# ConBoard_Top.net
KiCad netlist of a schematic drawn in Altium Designer
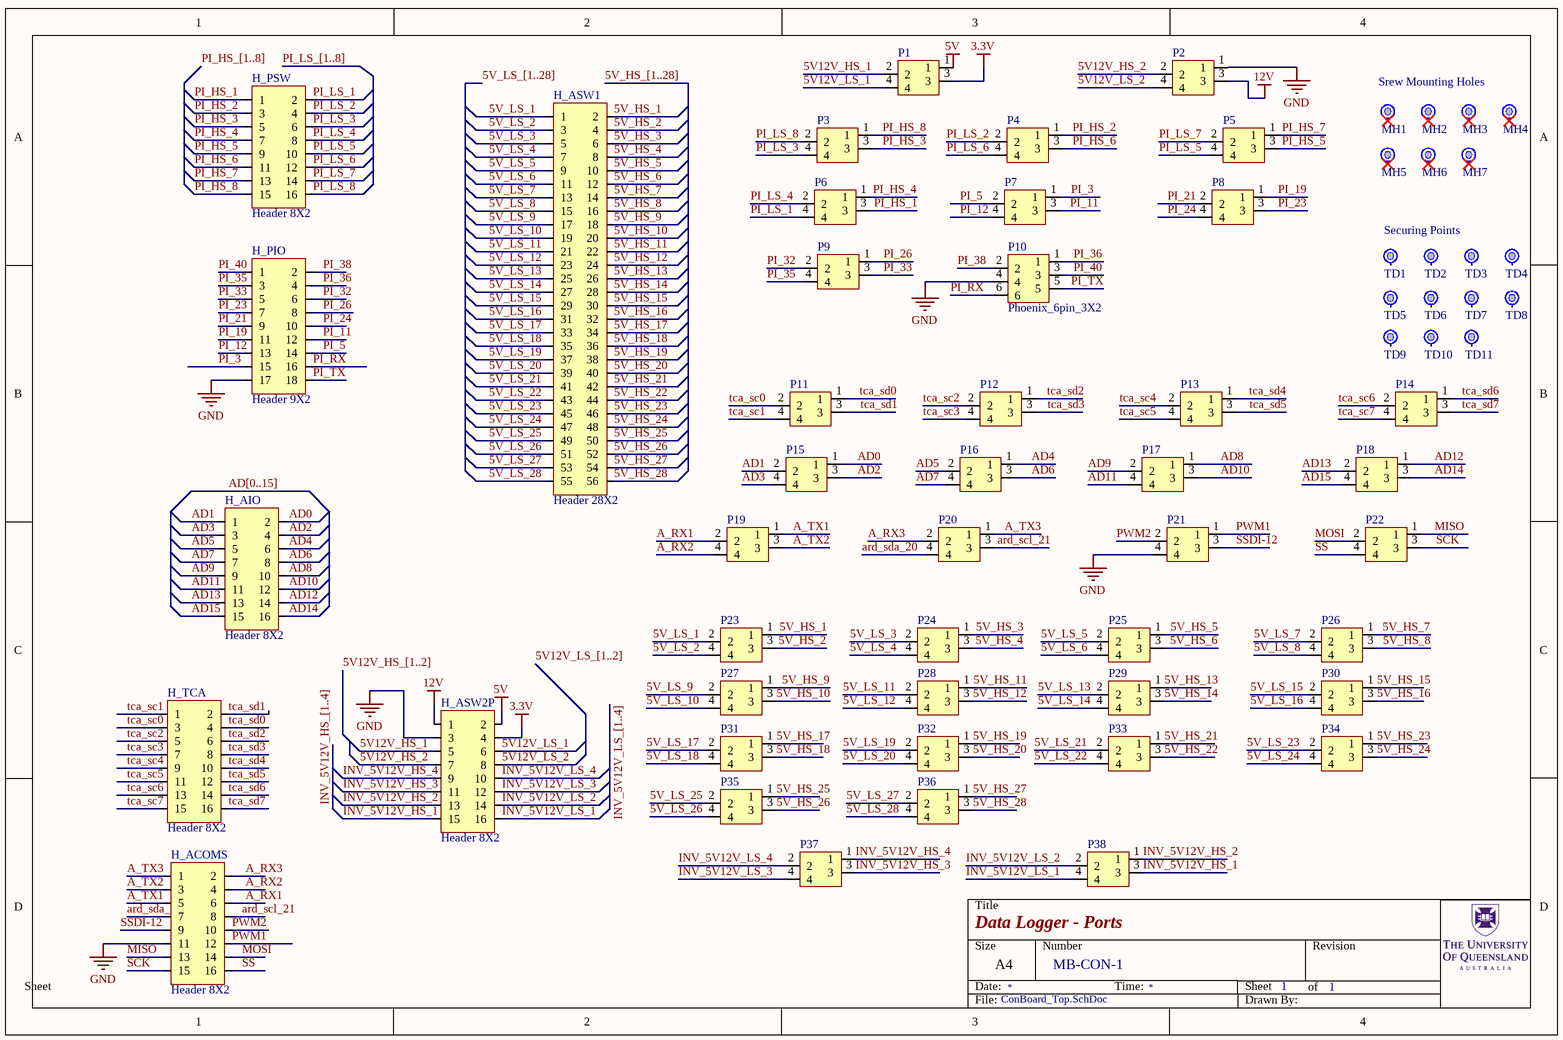
[diagram p0: ConBoard_Top.SchDoc]

(export (version "E")
  (design (tool "Eeschema 10.0.6"))
  (components
    (comp (ref "H_ACOMS")
      (value "Header 8X2")
      (footprint "HDR2X8")
      (description "Header, 8-Pin, Dual row")
      (fields (field (name "PUBLISHER") "Altium Limited"))
      (libsource (lib "Miscellaneous Connectors") (part "Header 8X2"))
    )
    (comp (ref "H_AIO")
      (value "Header 8X2")
      (footprint "HDR2X8")
      (description "Header, 8-Pin, Dual row")
      (fields (field (name "PUBLISHER") "Altium Limited"))
      (libsource (lib "Miscellaneous Connectors") (part "Header 8X2"))
    )
    (comp (ref "H_ASW1")
      (value "Header 28X2")
      (footprint "HDR2X28")
      (description "Header, 28-Pin, Dual row")
      (fields (field (name "PUBLISHER") "Altium Limited"))
      (libsource (lib "Data_logger_v3") (part "Header 28X2"))
    )
    (comp (ref "H_ASW2P")
      (value "Header 8X2")
      (footprint "HDR2X8")
      (description "Header, 8-Pin, Dual row")
      (fields (field (name "PUBLISHER") "Altium Limited"))
      (libsource (lib "Miscellaneous Connectors") (part "Header 8X2"))
    )
    (comp (ref "H_PIO")
      (value "Header 9X2")
      (footprint "HDR2X9")
      (description "Header, 9-Pin, Dual row")
      (fields (field (name "PUBLISHER") "Altium Limited"))
      (libsource (lib "Miscellaneous Connectors") (part "Header 9X2"))
    )
    (comp (ref "H_PSW")
      (value "Header 8X2")
      (footprint "HDR2X8")
      (description "Header, 8-Pin, Dual row")
      (fields (field (name "PUBLISHER") "Altium Limited"))
      (libsource (lib "Miscellaneous Connectors") (part "Header 8X2"))
    )
    (comp (ref "H_TCA")
      (value "Header 8X2")
      (footprint "HDR2X8")
      (description "Header, 8-Pin, Dual row")
      (fields (field (name "PUBLISHER") "Altium Limited"))
      (libsource (lib "Miscellaneous Connectors") (part "Header 8X2"))
    )
    (comp (ref "MH1")
      (value "MOUNTING_HOLE")
      (footprint "M3")
      (libsource (lib "Data_logger_v3") (part "MOUNTING_HOLE"))
    )
    (comp (ref "MH2")
      (value "MOUNTING_HOLE")
      (footprint "M3")
      (libsource (lib "Data_logger_v3") (part "MOUNTING_HOLE"))
    )
    (comp (ref "MH3")
      (value "MOUNTING_HOLE")
      (footprint "M3")
      (libsource (lib "Data_logger_v3") (part "MOUNTING_HOLE"))
    )
    (comp (ref "MH4")
      (value "MOUNTING_HOLE")
      (footprint "M3")
      (libsource (lib "Data_logger_v3") (part "MOUNTING_HOLE"))
    )
    (comp (ref "MH5")
      (value "MOUNTING_HOLE")
      (footprint "M3")
      (libsource (lib "Data_logger_v3") (part "MOUNTING_HOLE"))
    )
    (comp (ref "MH6")
      (value "MOUNTING_HOLE")
      (footprint "M3")
      (libsource (lib "Data_logger_v3") (part "MOUNTING_HOLE"))
    )
    (comp (ref "MH7")
      (value "MOUNTING_HOLE")
      (footprint "M3")
      (libsource (lib "Data_logger_v3") (part "MOUNTING_HOLE"))
    )
    (comp (ref "P1")
      (value "Phoenix_4pin_2X2")
      (footprint "MKKDSN_4PIN-2POS_5.08PITCH_1.5WIRE")
      (libsource (lib "Datalogger") (part "Phoenix_4pin_2X2"))
    )
    (comp (ref "P2")
      (value "Phoenix_4pin_2X2")
      (footprint "MKKDSN_4PIN-2POS_5.08PITCH_1.5WIRE")
      (libsource (lib "Datalogger") (part "Phoenix_4pin_2X2"))
    )
    (comp (ref "P3")
      (value "Phoenix_4pin_2X2")
      (footprint "MKKDSN_4PIN-2POS_5.08PITCH_1.5WIRE")
      (libsource (lib "Datalogger") (part "Phoenix_4pin_2X2"))
    )
    (comp (ref "P4")
      (value "Phoenix_4pin_2X2")
      (footprint "MKKDSN_4PIN-2POS_5.08PITCH_1.5WIRE")
      (libsource (lib "Datalogger") (part "Phoenix_4pin_2X2"))
    )
    (comp (ref "P5")
      (value "Phoenix_4pin_2X2")
      (footprint "MKKDSN_4PIN-2POS_5.08PITCH_1.5WIRE")
      (libsource (lib "Datalogger") (part "Phoenix_4pin_2X2"))
    )
    (comp (ref "P6")
      (value "Phoenix_4pin_2X2")
      (footprint "MKKDSN_4PIN-2POS_5.08PITCH_1.5WIRE")
      (libsource (lib "Datalogger") (part "Phoenix_4pin_2X2"))
    )
    (comp (ref "P7")
      (value "Phoenix_4pin_2X2")
      (footprint "MKKDSN_4PIN-2POS_5.08PITCH_1.5WIRE")
      (libsource (lib "Datalogger") (part "Phoenix_4pin_2X2"))
    )
    (comp (ref "P8")
      (value "Phoenix_4pin_2X2")
      (footprint "MKKDSN_4PIN-2POS_5.08PITCH_1.5WIRE")
      (libsource (lib "Datalogger") (part "Phoenix_4pin_2X2"))
    )
    (comp (ref "P9")
      (value "Phoenix_4pin_2X2")
      (footprint "MKKDSN_4PIN-2POS_5.08PITCH_1.5WIRE")
      (libsource (lib "Datalogger") (part "Phoenix_4pin_2X2"))
    )
    (comp (ref "P10")
      (value "Phoenix_6pin_3X2")
      (footprint "MKKDSN_6PIN-3POS_5.08PITCH_1.5WIRE")
      (libsource (lib "Datalogger") (part "Phoenix_6pin_3X2"))
    )
    (comp (ref "P11")
      (value "Phoenix_4pin_2X2")
      (footprint "MKKDSN_4PIN-2POS_5.08PITCH_1.5WIRE")
      (libsource (lib "Datalogger") (part "Phoenix_4pin_2X2"))
    )
    (comp (ref "P12")
      (value "Phoenix_4pin_2X2")
      (footprint "MKKDSN_4PIN-2POS_5.08PITCH_1.5WIRE")
      (libsource (lib "Datalogger") (part "Phoenix_4pin_2X2"))
    )
    (comp (ref "P13")
      (value "Phoenix_4pin_2X2")
      (footprint "MKKDSN_4PIN-2POS_5.08PITCH_1.5WIRE")
      (libsource (lib "Datalogger") (part "Phoenix_4pin_2X2"))
    )
    (comp (ref "P14")
      (value "Phoenix_4pin_2X2")
      (footprint "MKKDSN_4PIN-2POS_5.08PITCH_1.5WIRE")
      (libsource (lib "Datalogger") (part "Phoenix_4pin_2X2"))
    )
    (comp (ref "P15")
      (value "Phoenix_4pin_2X2")
      (footprint "MKKDSN_4PIN-2POS_5.08PITCH_1.5WIRE")
      (libsource (lib "Datalogger") (part "Phoenix_4pin_2X2"))
    )
    (comp (ref "P16")
      (value "Phoenix_4pin_2X2")
      (footprint "MKKDSN_4PIN-2POS_5.08PITCH_1.5WIRE")
      (libsource (lib "Datalogger") (part "Phoenix_4pin_2X2"))
    )
    (comp (ref "P17")
      (value "Phoenix_4pin_2X2")
      (footprint "MKKDSN_4PIN-2POS_5.08PITCH_1.5WIRE")
      (libsource (lib "Datalogger") (part "Phoenix_4pin_2X2"))
    )
    (comp (ref "P18")
      (value "Phoenix_4pin_2X2")
      (footprint "MKKDSN_4PIN-2POS_5.08PITCH_1.5WIRE")
      (libsource (lib "Datalogger") (part "Phoenix_4pin_2X2"))
    )
    (comp (ref "P19")
      (value "Phoenix_4pin_2X2")
      (footprint "MKKDSN_4PIN-2POS_5.08PITCH_1.5WIRE")
      (libsource (lib "Datalogger") (part "Phoenix_4pin_2X2"))
    )
    (comp (ref "P20")
      (value "Phoenix_4pin_2X2")
      (footprint "MKKDSN_4PIN-2POS_5.08PITCH_1.5WIRE")
      (libsource (lib "Datalogger") (part "Phoenix_4pin_2X2"))
    )
    (comp (ref "P21")
      (value "Phoenix_4pin_2X2")
      (footprint "MKKDSN_4PIN-2POS_5.08PITCH_1.5WIRE")
      (libsource (lib "Datalogger") (part "Phoenix_4pin_2X2"))
    )
    (comp (ref "P22")
      (value "Phoenix_4pin_2X2")
      (footprint "MKKDSN_4PIN-2POS_5.08PITCH_1.5WIRE")
      (libsource (lib "Datalogger") (part "Phoenix_4pin_2X2"))
    )
    (comp (ref "P23")
      (value "Phoenix_4pin_2X2")
      (footprint "MKKDSN_4PIN-2POS_5.08PITCH_1.5WIRE")
      (libsource (lib "Datalogger") (part "Phoenix_4pin_2X2"))
    )
    (comp (ref "P24")
      (value "Phoenix_4pin_2X2")
      (footprint "MKKDSN_4PIN-2POS_5.08PITCH_1.5WIRE")
      (libsource (lib "Datalogger") (part "Phoenix_4pin_2X2"))
    )
    (comp (ref "P25")
      (value "Phoenix_4pin_2X2")
      (footprint "MKKDSN_4PIN-2POS_5.08PITCH_1.5WIRE")
      (libsource (lib "Datalogger") (part "Phoenix_4pin_2X2"))
    )
    (comp (ref "P26")
      (value "Phoenix_4pin_2X2")
      (footprint "MKKDSN_4PIN-2POS_5.08PITCH_1.5WIRE")
      (libsource (lib "Datalogger") (part "Phoenix_4pin_2X2"))
    )
    (comp (ref "P27")
      (value "Phoenix_4pin_2X2")
      (footprint "MKKDSN_4PIN-2POS_5.08PITCH_1.5WIRE")
      (libsource (lib "Datalogger") (part "Phoenix_4pin_2X2"))
    )
    (comp (ref "P28")
      (value "Phoenix_4pin_2X2")
      (footprint "MKKDSN_4PIN-2POS_5.08PITCH_1.5WIRE")
      (libsource (lib "Datalogger") (part "Phoenix_4pin_2X2"))
    )
    (comp (ref "P29")
      (value "Phoenix_4pin_2X2")
      (footprint "MKKDSN_4PIN-2POS_5.08PITCH_1.5WIRE")
      (libsource (lib "Datalogger") (part "Phoenix_4pin_2X2"))
    )
    (comp (ref "P30")
      (value "Phoenix_4pin_2X2")
      (footprint "MKKDSN_4PIN-2POS_5.08PITCH_1.5WIRE")
      (libsource (lib "Datalogger") (part "Phoenix_4pin_2X2"))
    )
    (comp (ref "P31")
      (value "Phoenix_4pin_2X2")
      (footprint "MKKDSN_4PIN-2POS_5.08PITCH_1.5WIRE")
      (libsource (lib "Datalogger") (part "Phoenix_4pin_2X2"))
    )
    (comp (ref "P32")
      (value "Phoenix_4pin_2X2")
      (footprint "MKKDSN_4PIN-2POS_5.08PITCH_1.5WIRE")
      (libsource (lib "Datalogger") (part "Phoenix_4pin_2X2"))
    )
    (comp (ref "P33")
      (value "Phoenix_4pin_2X2")
      (footprint "MKKDSN_4PIN-2POS_5.08PITCH_1.5WIRE")
      (libsource (lib "Datalogger") (part "Phoenix_4pin_2X2"))
    )
    (comp (ref "P34")
      (value "Phoenix_4pin_2X2")
      (footprint "MKKDSN_4PIN-2POS_5.08PITCH_1.5WIRE")
      (libsource (lib "Datalogger") (part "Phoenix_4pin_2X2"))
    )
    (comp (ref "P35")
      (value "Phoenix_4pin_2X2")
      (footprint "MKKDSN_4PIN-2POS_5.08PITCH_1.5WIRE")
      (libsource (lib "Datalogger") (part "Phoenix_4pin_2X2"))
    )
    (comp (ref "P36")
      (value "Phoenix_4pin_2X2")
      (footprint "MKKDSN_4PIN-2POS_5.08PITCH_1.5WIRE")
      (libsource (lib "Datalogger") (part "Phoenix_4pin_2X2"))
    )
    (comp (ref "P37")
      (value "Phoenix_4pin_2X2")
      (footprint "MKKDSN_4PIN-2POS_5.08PITCH_1.5WIRE")
      (libsource (lib "Datalogger") (part "Phoenix_4pin_2X2"))
    )
    (comp (ref "P38")
      (value "Phoenix_4pin_2X2")
      (footprint "MKKDSN_4PIN-2POS_5.08PITCH_1.5WIRE")
      (libsource (lib "Datalogger") (part "Phoenix_4pin_2X2"))
    )
    (comp (ref "TD1")
      (value "TIEDOWNS")
      (footprint "M3")
      (libsource (lib "Data_logger_v3") (part "MOUNTING_HOLE"))
    )
    (comp (ref "TD2")
      (value "TIEDOWNS")
      (footprint "M3")
      (libsource (lib "Data_logger_v3") (part "MOUNTING_HOLE"))
    )
    (comp (ref "TD3")
      (value "TIEDOWNS")
      (footprint "M3")
      (libsource (lib "Data_logger_v3") (part "MOUNTING_HOLE"))
    )
    (comp (ref "TD4")
      (value "TIEDOWNS")
      (footprint "M3")
      (libsource (lib "Data_logger_v3") (part "MOUNTING_HOLE"))
    )
    (comp (ref "TD5")
      (value "TIEDOWNS")
      (footprint "M3")
      (libsource (lib "Data_logger_v3") (part "MOUNTING_HOLE"))
    )
    (comp (ref "TD6")
      (value "TIEDOWNS")
      (footprint "M3")
      (libsource (lib "Data_logger_v3") (part "MOUNTING_HOLE"))
    )
    (comp (ref "TD7")
      (value "TIEDOWNS")
      (footprint "M3")
      (libsource (lib "Data_logger_v3") (part "MOUNTING_HOLE"))
    )
    (comp (ref "TD8")
      (value "TIEDOWNS")
      (footprint "M3")
      (libsource (lib "Data_logger_v3") (part "MOUNTING_HOLE"))
    )
    (comp (ref "TD9")
      (value "TIEDOWNS")
      (footprint "M3")
      (libsource (lib "Data_logger_v3") (part "MOUNTING_HOLE"))
    )
    (comp (ref "TD10")
      (value "TIEDOWNS")
      (footprint "M3")
      (libsource (lib "Data_logger_v3") (part "MOUNTING_HOLE"))
    )
    (comp (ref "TD11")
      (value "TIEDOWNS")
      (footprint "M3")
      (libsource (lib "Data_logger_v3") (part "MOUNTING_HOLE"))
    )
  )
  (nets
    (net (code "1") (name "/5V12V_HS_1") (class "Default")
      (node (ref "H_ASW2P") (pin "5") (pinfunction "5_5") (pintype "passive"))
      (node (ref "P1") (pin "2") (pinfunction "2_2") (pintype "passive"))
    )
    (net (code "2") (name "/5V12V_HS_2") (class "Default")
      (node (ref "H_ASW2P") (pin "7") (pinfunction "7_7") (pintype "passive"))
      (node (ref "P2") (pin "2") (pinfunction "2_2") (pintype "passive"))
    )
    (net (code "4") (name "/5V12V_LS_1") (class "Default")
      (node (ref "H_ASW2P") (pin "6") (pinfunction "6_6") (pintype "passive"))
      (node (ref "P1") (pin "4") (pinfunction "4_4") (pintype "passive"))
    )
    (net (code "5") (name "/5V12V_LS_2") (class "Default")
      (node (ref "H_ASW2P") (pin "8") (pinfunction "8_8") (pintype "passive"))
      (node (ref "P2") (pin "4") (pinfunction "4_4") (pintype "passive"))
    )
    (net (code "7") (name "/5V_HS_1") (class "Default")
      (node (ref "H_ASW1") (pin "2") (pinfunction "2_2") (pintype "passive"))
      (node (ref "P23") (pin "1") (pinfunction "1_1") (pintype "passive"))
    )
    (net (code "8") (name "/5V_HS_2") (class "Default")
      (node (ref "H_ASW1") (pin "4") (pinfunction "4_4") (pintype "passive"))
      (node (ref "P23") (pin "3") (pinfunction "3_3") (pintype "passive"))
    )
    (net (code "9") (name "/5V_HS_3") (class "Default")
      (node (ref "H_ASW1") (pin "6") (pinfunction "6_6") (pintype "passive"))
      (node (ref "P24") (pin "1") (pinfunction "1_1") (pintype "passive"))
    )
    (net (code "10") (name "/5V_HS_4") (class "Default")
      (node (ref "H_ASW1") (pin "8") (pinfunction "8_8") (pintype "passive"))
      (node (ref "P24") (pin "3") (pinfunction "3_3") (pintype "passive"))
    )
    (net (code "11") (name "/5V_HS_5") (class "Default")
      (node (ref "H_ASW1") (pin "10") (pinfunction "10_10") (pintype "passive"))
      (node (ref "P25") (pin "1") (pinfunction "1_1") (pintype "passive"))
    )
    (net (code "12") (name "/5V_HS_6") (class "Default")
      (node (ref "H_ASW1") (pin "12") (pinfunction "12_12") (pintype "passive"))
      (node (ref "P25") (pin "3") (pinfunction "3_3") (pintype "passive"))
    )
    (net (code "13") (name "/5V_HS_7") (class "Default")
      (node (ref "H_ASW1") (pin "14") (pinfunction "14_14") (pintype "passive"))
      (node (ref "P26") (pin "1") (pinfunction "1_1") (pintype "passive"))
    )
    (net (code "14") (name "/5V_HS_8") (class "Default")
      (node (ref "H_ASW1") (pin "16") (pinfunction "16_16") (pintype "passive"))
      (node (ref "P26") (pin "3") (pinfunction "3_3") (pintype "passive"))
    )
    (net (code "15") (name "/5V_HS_9") (class "Default")
      (node (ref "H_ASW1") (pin "18") (pinfunction "18_18") (pintype "passive"))
      (node (ref "P27") (pin "1") (pinfunction "1_1") (pintype "passive"))
    )
    (net (code "16") (name "/5V_HS_10") (class "Default")
      (node (ref "H_ASW1") (pin "20") (pinfunction "20_20") (pintype "passive"))
      (node (ref "P27") (pin "3") (pinfunction "3_3") (pintype "passive"))
    )
    (net (code "17") (name "/5V_HS_11") (class "Default")
      (node (ref "H_ASW1") (pin "22") (pinfunction "22_22") (pintype "passive"))
      (node (ref "P28") (pin "1") (pinfunction "1_1") (pintype "passive"))
    )
    (net (code "18") (name "/5V_HS_12") (class "Default")
      (node (ref "H_ASW1") (pin "24") (pinfunction "24_24") (pintype "passive"))
      (node (ref "P28") (pin "3") (pinfunction "3_3") (pintype "passive"))
    )
    (net (code "19") (name "/5V_HS_13") (class "Default")
      (node (ref "H_ASW1") (pin "26") (pinfunction "26_26") (pintype "passive"))
      (node (ref "P29") (pin "1") (pinfunction "1_1") (pintype "passive"))
    )
    (net (code "20") (name "/5V_HS_14") (class "Default")
      (node (ref "H_ASW1") (pin "28") (pinfunction "28_28") (pintype "passive"))
      (node (ref "P29") (pin "3") (pinfunction "3_3") (pintype "passive"))
    )
    (net (code "21") (name "/5V_HS_15") (class "Default")
      (node (ref "H_ASW1") (pin "30") (pinfunction "30_30") (pintype "passive"))
      (node (ref "P30") (pin "1") (pinfunction "1_1") (pintype "passive"))
    )
    (net (code "22") (name "/5V_HS_16") (class "Default")
      (node (ref "H_ASW1") (pin "32") (pinfunction "32_32") (pintype "passive"))
      (node (ref "P30") (pin "3") (pinfunction "3_3") (pintype "passive"))
    )
    (net (code "23") (name "/5V_HS_17") (class "Default")
      (node (ref "H_ASW1") (pin "34") (pinfunction "34_34") (pintype "passive"))
      (node (ref "P31") (pin "1") (pinfunction "1_1") (pintype "passive"))
    )
    (net (code "24") (name "/5V_HS_18") (class "Default")
      (node (ref "H_ASW1") (pin "36") (pinfunction "36_36") (pintype "passive"))
      (node (ref "P31") (pin "3") (pinfunction "3_3") (pintype "passive"))
    )
    (net (code "25") (name "/5V_HS_19") (class "Default")
      (node (ref "H_ASW1") (pin "38") (pinfunction "38_38") (pintype "passive"))
      (node (ref "P32") (pin "1") (pinfunction "1_1") (pintype "passive"))
    )
    (net (code "26") (name "/5V_HS_20") (class "Default")
      (node (ref "H_ASW1") (pin "40") (pinfunction "40_40") (pintype "passive"))
      (node (ref "P32") (pin "3") (pinfunction "3_3") (pintype "passive"))
    )
    (net (code "27") (name "/5V_HS_21") (class "Default")
      (node (ref "H_ASW1") (pin "42") (pinfunction "42_42") (pintype "passive"))
      (node (ref "P33") (pin "1") (pinfunction "1_1") (pintype "passive"))
    )
    (net (code "28") (name "/5V_HS_22") (class "Default")
      (node (ref "H_ASW1") (pin "44") (pinfunction "44_44") (pintype "passive"))
      (node (ref "P33") (pin "3") (pinfunction "3_3") (pintype "passive"))
    )
    (net (code "29") (name "/5V_HS_23") (class "Default")
      (node (ref "H_ASW1") (pin "46") (pinfunction "46_46") (pintype "passive"))
      (node (ref "P34") (pin "1") (pinfunction "1_1") (pintype "passive"))
    )
    (net (code "30") (name "/5V_HS_24") (class "Default")
      (node (ref "H_ASW1") (pin "48") (pinfunction "48_48") (pintype "passive"))
      (node (ref "P34") (pin "3") (pinfunction "3_3") (pintype "passive"))
    )
    (net (code "31") (name "/5V_HS_25") (class "Default")
      (node (ref "H_ASW1") (pin "50") (pinfunction "50_50") (pintype "passive"))
      (node (ref "P35") (pin "1") (pinfunction "1_1") (pintype "passive"))
    )
    (net (code "32") (name "/5V_HS_26") (class "Default")
      (node (ref "H_ASW1") (pin "52") (pinfunction "52_52") (pintype "passive"))
      (node (ref "P35") (pin "3") (pinfunction "3_3") (pintype "passive"))
    )
    (net (code "33") (name "/5V_HS_27") (class "Default")
      (node (ref "H_ASW1") (pin "54") (pinfunction "54_54") (pintype "passive"))
      (node (ref "P36") (pin "1") (pinfunction "1_1") (pintype "passive"))
    )
    (net (code "34") (name "/5V_HS_28") (class "Default")
      (node (ref "H_ASW1") (pin "56") (pinfunction "56_56") (pintype "passive"))
      (node (ref "P36") (pin "3") (pinfunction "3_3") (pintype "passive"))
    )
    (net (code "36") (name "/5V_LS_1") (class "Default")
      (node (ref "H_ASW1") (pin "1") (pinfunction "1_1") (pintype "passive"))
      (node (ref "P23") (pin "2") (pinfunction "2_2") (pintype "passive"))
    )
    (net (code "37") (name "/5V_LS_2") (class "Default")
      (node (ref "H_ASW1") (pin "3") (pinfunction "3_3") (pintype "passive"))
      (node (ref "P23") (pin "4") (pinfunction "4_4") (pintype "passive"))
    )
    (net (code "38") (name "/5V_LS_3") (class "Default")
      (node (ref "H_ASW1") (pin "5") (pinfunction "5_5") (pintype "passive"))
      (node (ref "P24") (pin "2") (pinfunction "2_2") (pintype "passive"))
    )
    (net (code "39") (name "/5V_LS_4") (class "Default")
      (node (ref "H_ASW1") (pin "7") (pinfunction "7_7") (pintype "passive"))
      (node (ref "P24") (pin "4") (pinfunction "4_4") (pintype "passive"))
    )
    (net (code "40") (name "/5V_LS_5") (class "Default")
      (node (ref "H_ASW1") (pin "9") (pinfunction "9_9") (pintype "passive"))
      (node (ref "P25") (pin "2") (pinfunction "2_2") (pintype "passive"))
    )
    (net (code "41") (name "/5V_LS_6") (class "Default")
      (node (ref "H_ASW1") (pin "11") (pinfunction "11_11") (pintype "passive"))
      (node (ref "P25") (pin "4") (pinfunction "4_4") (pintype "passive"))
    )
    (net (code "42") (name "/5V_LS_7") (class "Default")
      (node (ref "H_ASW1") (pin "13") (pinfunction "13_13") (pintype "passive"))
      (node (ref "P26") (pin "2") (pinfunction "2_2") (pintype "passive"))
    )
    (net (code "43") (name "/5V_LS_8") (class "Default")
      (node (ref "H_ASW1") (pin "15") (pinfunction "15_15") (pintype "passive"))
      (node (ref "P26") (pin "4") (pinfunction "4_4") (pintype "passive"))
    )
    (net (code "44") (name "/5V_LS_9") (class "Default")
      (node (ref "H_ASW1") (pin "17") (pinfunction "17_17") (pintype "passive"))
      (node (ref "P27") (pin "2") (pinfunction "2_2") (pintype "passive"))
    )
    (net (code "45") (name "/5V_LS_10") (class "Default")
      (node (ref "H_ASW1") (pin "19") (pinfunction "19_19") (pintype "passive"))
      (node (ref "P27") (pin "4") (pinfunction "4_4") (pintype "passive"))
    )
    (net (code "46") (name "/5V_LS_11") (class "Default")
      (node (ref "H_ASW1") (pin "21") (pinfunction "21_21") (pintype "passive"))
      (node (ref "P28") (pin "2") (pinfunction "2_2") (pintype "passive"))
    )
    (net (code "47") (name "/5V_LS_12") (class "Default")
      (node (ref "H_ASW1") (pin "23") (pinfunction "23_23") (pintype "passive"))
      (node (ref "P28") (pin "4") (pinfunction "4_4") (pintype "passive"))
    )
    (net (code "48") (name "/5V_LS_13") (class "Default")
      (node (ref "H_ASW1") (pin "25") (pinfunction "25_25") (pintype "passive"))
      (node (ref "P29") (pin "2") (pinfunction "2_2") (pintype "passive"))
    )
    (net (code "49") (name "/5V_LS_14") (class "Default")
      (node (ref "H_ASW1") (pin "27") (pinfunction "27_27") (pintype "passive"))
      (node (ref "P29") (pin "4") (pinfunction "4_4") (pintype "passive"))
    )
    (net (code "50") (name "/5V_LS_15") (class "Default")
      (node (ref "H_ASW1") (pin "29") (pinfunction "29_29") (pintype "passive"))
      (node (ref "P30") (pin "2") (pinfunction "2_2") (pintype "passive"))
    )
    (net (code "51") (name "/5V_LS_16") (class "Default")
      (node (ref "H_ASW1") (pin "31") (pinfunction "31_31") (pintype "passive"))
      (node (ref "P30") (pin "4") (pinfunction "4_4") (pintype "passive"))
    )
    (net (code "52") (name "/5V_LS_17") (class "Default")
      (node (ref "H_ASW1") (pin "33") (pinfunction "33_33") (pintype "passive"))
      (node (ref "P31") (pin "2") (pinfunction "2_2") (pintype "passive"))
    )
    (net (code "53") (name "/5V_LS_18") (class "Default")
      (node (ref "H_ASW1") (pin "35") (pinfunction "35_35") (pintype "passive"))
      (node (ref "P31") (pin "4") (pinfunction "4_4") (pintype "passive"))
    )
    (net (code "54") (name "/5V_LS_19") (class "Default")
      (node (ref "H_ASW1") (pin "37") (pinfunction "37_37") (pintype "passive"))
      (node (ref "P32") (pin "2") (pinfunction "2_2") (pintype "passive"))
    )
    (net (code "55") (name "/5V_LS_20") (class "Default")
      (node (ref "H_ASW1") (pin "39") (pinfunction "39_39") (pintype "passive"))
      (node (ref "P32") (pin "4") (pinfunction "4_4") (pintype "passive"))
    )
    (net (code "56") (name "/5V_LS_21") (class "Default")
      (node (ref "H_ASW1") (pin "41") (pinfunction "41_41") (pintype "passive"))
      (node (ref "P33") (pin "2") (pinfunction "2_2") (pintype "passive"))
    )
    (net (code "57") (name "/5V_LS_22") (class "Default")
      (node (ref "H_ASW1") (pin "43") (pinfunction "43_43") (pintype "passive"))
      (node (ref "P33") (pin "4") (pinfunction "4_4") (pintype "passive"))
    )
    (net (code "58") (name "/5V_LS_23") (class "Default")
      (node (ref "H_ASW1") (pin "45") (pinfunction "45_45") (pintype "passive"))
      (node (ref "P34") (pin "2") (pinfunction "2_2") (pintype "passive"))
    )
    (net (code "59") (name "/5V_LS_24") (class "Default")
      (node (ref "H_ASW1") (pin "47") (pinfunction "47_47") (pintype "passive"))
      (node (ref "P34") (pin "4") (pinfunction "4_4") (pintype "passive"))
    )
    (net (code "60") (name "/5V_LS_25") (class "Default")
      (node (ref "H_ASW1") (pin "49") (pinfunction "49_49") (pintype "passive"))
      (node (ref "P35") (pin "2") (pinfunction "2_2") (pintype "passive"))
    )
    (net (code "61") (name "/5V_LS_26") (class "Default")
      (node (ref "H_ASW1") (pin "51") (pinfunction "51_51") (pintype "passive"))
      (node (ref "P35") (pin "4") (pinfunction "4_4") (pintype "passive"))
    )
    (net (code "62") (name "/5V_LS_27") (class "Default")
      (node (ref "H_ASW1") (pin "53") (pinfunction "53_53") (pintype "passive"))
      (node (ref "P36") (pin "2") (pinfunction "2_2") (pintype "passive"))
    )
    (net (code "63") (name "/5V_LS_28") (class "Default")
      (node (ref "H_ASW1") (pin "55") (pinfunction "55_55") (pintype "passive"))
      (node (ref "P36") (pin "4") (pinfunction "4_4") (pintype "passive"))
    )
    (net (code "65") (name "/AD0") (class "Default")
      (node (ref "H_AIO") (pin "2") (pinfunction "2_2") (pintype "passive"))
      (node (ref "P15") (pin "1") (pinfunction "1_1") (pintype "passive"))
    )
    (net (code "66") (name "/AD1") (class "Default")
      (node (ref "H_AIO") (pin "1") (pinfunction "1_1") (pintype "passive"))
      (node (ref "P15") (pin "2") (pinfunction "2_2") (pintype "passive"))
    )
    (net (code "67") (name "/AD2") (class "Default")
      (node (ref "H_AIO") (pin "4") (pinfunction "4_4") (pintype "passive"))
      (node (ref "P15") (pin "3") (pinfunction "3_3") (pintype "passive"))
    )
    (net (code "68") (name "/AD3") (class "Default")
      (node (ref "H_AIO") (pin "3") (pinfunction "3_3") (pintype "passive"))
      (node (ref "P15") (pin "4") (pinfunction "4_4") (pintype "passive"))
    )
    (net (code "69") (name "/AD4") (class "Default")
      (node (ref "H_AIO") (pin "6") (pinfunction "6_6") (pintype "passive"))
      (node (ref "P16") (pin "1") (pinfunction "1_1") (pintype "passive"))
    )
    (net (code "70") (name "/AD5") (class "Default")
      (node (ref "H_AIO") (pin "5") (pinfunction "5_5") (pintype "passive"))
      (node (ref "P16") (pin "2") (pinfunction "2_2") (pintype "passive"))
    )
    (net (code "71") (name "/AD6") (class "Default")
      (node (ref "H_AIO") (pin "8") (pinfunction "8_8") (pintype "passive"))
      (node (ref "P16") (pin "3") (pinfunction "3_3") (pintype "passive"))
    )
    (net (code "72") (name "/AD7") (class "Default")
      (node (ref "H_AIO") (pin "7") (pinfunction "7_7") (pintype "passive"))
      (node (ref "P16") (pin "4") (pinfunction "4_4") (pintype "passive"))
    )
    (net (code "73") (name "/AD8") (class "Default")
      (node (ref "H_AIO") (pin "10") (pinfunction "10_10") (pintype "passive"))
      (node (ref "P17") (pin "1") (pinfunction "1_1") (pintype "passive"))
    )
    (net (code "74") (name "/AD9") (class "Default")
      (node (ref "H_AIO") (pin "9") (pinfunction "9_9") (pintype "passive"))
      (node (ref "P17") (pin "2") (pinfunction "2_2") (pintype "passive"))
    )
    (net (code "75") (name "/AD10") (class "Default")
      (node (ref "H_AIO") (pin "12") (pinfunction "12_12") (pintype "passive"))
      (node (ref "P17") (pin "3") (pinfunction "3_3") (pintype "passive"))
    )
    (net (code "76") (name "/AD11") (class "Default")
      (node (ref "H_AIO") (pin "11") (pinfunction "11_11") (pintype "passive"))
      (node (ref "P17") (pin "4") (pinfunction "4_4") (pintype "passive"))
    )
    (net (code "77") (name "/AD12") (class "Default")
      (node (ref "H_AIO") (pin "14") (pinfunction "14_14") (pintype "passive"))
      (node (ref "P18") (pin "1") (pinfunction "1_1") (pintype "passive"))
    )
    (net (code "78") (name "/AD13") (class "Default")
      (node (ref "H_AIO") (pin "13") (pinfunction "13_13") (pintype "passive"))
      (node (ref "P18") (pin "2") (pinfunction "2_2") (pintype "passive"))
    )
    (net (code "79") (name "/AD14") (class "Default")
      (node (ref "H_AIO") (pin "16") (pinfunction "16_16") (pintype "passive"))
      (node (ref "P18") (pin "3") (pinfunction "3_3") (pintype "passive"))
    )
    (net (code "80") (name "/AD15") (class "Default")
      (node (ref "H_AIO") (pin "15") (pinfunction "15_15") (pintype "passive"))
      (node (ref "P18") (pin "4") (pinfunction "4_4") (pintype "passive"))
    )
    (net (code "82") (name "/A_RX1") (class "Default")
      (node (ref "H_ACOMS") (pin "6") (pinfunction "6_6") (pintype "passive"))
      (node (ref "P19") (pin "2") (pinfunction "2_2") (pintype "passive"))
    )
    (net (code "83") (name "/A_RX2") (class "Default")
      (node (ref "H_ACOMS") (pin "4") (pinfunction "4_4") (pintype "passive"))
      (node (ref "P19") (pin "4") (pinfunction "4_4") (pintype "passive"))
    )
    (net (code "84") (name "/A_RX3") (class "Default")
      (node (ref "H_ACOMS") (pin "2") (pinfunction "2_2") (pintype "passive"))
      (node (ref "P20") (pin "2") (pinfunction "2_2") (pintype "passive"))
    )
    (net (code "85") (name "/A_TX1") (class "Default")
      (node (ref "H_ACOMS") (pin "5") (pinfunction "5_5") (pintype "passive"))
      (node (ref "P19") (pin "1") (pinfunction "1_1") (pintype "passive"))
    )
    (net (code "86") (name "/A_TX2") (class "Default")
      (node (ref "H_ACOMS") (pin "3") (pinfunction "3_3") (pintype "passive"))
      (node (ref "P19") (pin "3") (pinfunction "3_3") (pintype "passive"))
    )
    (net (code "87") (name "/A_TX3") (class "Default")
      (node (ref "H_ACOMS") (pin "1") (pinfunction "1_1") (pintype "passive"))
      (node (ref "P20") (pin "1") (pinfunction "1_1") (pintype "passive"))
    )
    (net (code "88") (name "/INV_5V12V_HS_1") (class "Default")
      (node (ref "H_ASW2P") (pin "15") (pinfunction "15_15") (pintype "passive"))
      (node (ref "P38") (pin "3") (pinfunction "3_3") (pintype "passive"))
    )
    (net (code "89") (name "/INV_5V12V_HS_2") (class "Default")
      (node (ref "H_ASW2P") (pin "13") (pinfunction "13_13") (pintype "passive"))
      (node (ref "P38") (pin "1") (pinfunction "1_1") (pintype "passive"))
    )
    (net (code "90") (name "/INV_5V12V_HS_3") (class "Default")
      (node (ref "H_ASW2P") (pin "11") (pinfunction "11_11") (pintype "passive"))
      (node (ref "P37") (pin "3") (pinfunction "3_3") (pintype "passive"))
    )
    (net (code "91") (name "/INV_5V12V_HS_4") (class "Default")
      (node (ref "H_ASW2P") (pin "9") (pinfunction "9_9") (pintype "passive"))
      (node (ref "P37") (pin "1") (pinfunction "1_1") (pintype "passive"))
    )
    (net (code "93") (name "/INV_5V12V_LS_1") (class "Default")
      (node (ref "H_ASW2P") (pin "16") (pinfunction "16_16") (pintype "passive"))
      (node (ref "P38") (pin "4") (pinfunction "4_4") (pintype "passive"))
    )
    (net (code "94") (name "/INV_5V12V_LS_2") (class "Default")
      (node (ref "H_ASW2P") (pin "14") (pinfunction "14_14") (pintype "passive"))
      (node (ref "P38") (pin "2") (pinfunction "2_2") (pintype "passive"))
    )
    (net (code "95") (name "/INV_5V12V_LS_3") (class "Default")
      (node (ref "H_ASW2P") (pin "12") (pinfunction "12_12") (pintype "passive"))
      (node (ref "P37") (pin "4") (pinfunction "4_4") (pintype "passive"))
    )
    (net (code "96") (name "/INV_5V12V_LS_4") (class "Default")
      (node (ref "H_ASW2P") (pin "10") (pinfunction "10_10") (pintype "passive"))
      (node (ref "P37") (pin "2") (pinfunction "2_2") (pintype "passive"))
    )
    (net (code "98") (name "/MISO") (class "Default")
      (node (ref "H_ACOMS") (pin "13") (pinfunction "13_13") (pintype "passive"))
      (node (ref "P22") (pin "1") (pinfunction "1_1") (pintype "passive"))
    )
    (net (code "99") (name "/MOSI") (class "Default")
      (node (ref "H_ACOMS") (pin "14") (pinfunction "14_14") (pintype "passive"))
      (node (ref "P22") (pin "2") (pinfunction "2_2") (pintype "passive"))
    )
    (net (code "100") (name "/PI_3") (class "Default")
      (node (ref "H_PIO") (pin "15") (pinfunction "15_15") (pintype "passive"))
      (node (ref "P7") (pin "1") (pinfunction "1_1") (pintype "passive"))
    )
    (net (code "101") (name "/PI_5") (class "Default")
      (node (ref "H_PIO") (pin "14") (pinfunction "14_14") (pintype "passive"))
      (node (ref "P7") (pin "2") (pinfunction "2_2") (pintype "passive"))
    )
    (net (code "102") (name "/PI_11") (class "Default")
      (node (ref "H_PIO") (pin "12") (pinfunction "12_12") (pintype "passive"))
      (node (ref "P7") (pin "3") (pinfunction "3_3") (pintype "passive"))
    )
    (net (code "103") (name "/PI_12") (class "Default")
      (node (ref "H_PIO") (pin "13") (pinfunction "13_13") (pintype "passive"))
      (node (ref "P7") (pin "4") (pinfunction "4_4") (pintype "passive"))
    )
    (net (code "104") (name "/PI_19") (class "Default")
      (node (ref "H_PIO") (pin "11") (pinfunction "11_11") (pintype "passive"))
      (node (ref "P8") (pin "1") (pinfunction "1_1") (pintype "passive"))
    )
    (net (code "105") (name "/PI_21") (class "Default")
      (node (ref "H_PIO") (pin "9") (pinfunction "9_9") (pintype "passive"))
      (node (ref "P8") (pin "2") (pinfunction "2_2") (pintype "passive"))
    )
    (net (code "106") (name "/PI_23") (class "Default")
      (node (ref "H_PIO") (pin "7") (pinfunction "7_7") (pintype "passive"))
      (node (ref "P8") (pin "3") (pinfunction "3_3") (pintype "passive"))
    )
    (net (code "107") (name "/PI_24") (class "Default")
      (node (ref "H_PIO") (pin "10") (pinfunction "10_10") (pintype "passive"))
      (node (ref "P8") (pin "4") (pinfunction "4_4") (pintype "passive"))
    )
    (net (code "108") (name "/PI_26") (class "Default")
      (node (ref "H_PIO") (pin "8") (pinfunction "8_8") (pintype "passive"))
      (node (ref "P9") (pin "1") (pinfunction "1_1") (pintype "passive"))
    )
    (net (code "109") (name "/PI_32") (class "Default")
      (node (ref "H_PIO") (pin "6") (pinfunction "6_6") (pintype "passive"))
      (node (ref "P9") (pin "2") (pinfunction "2_2") (pintype "passive"))
    )
    (net (code "110") (name "/PI_33") (class "Default")
      (node (ref "H_PIO") (pin "5") (pinfunction "5_5") (pintype "passive"))
      (node (ref "P9") (pin "3") (pinfunction "3_3") (pintype "passive"))
    )
    (net (code "111") (name "/PI_35") (class "Default")
      (node (ref "H_PIO") (pin "3") (pinfunction "3_3") (pintype "passive"))
      (node (ref "P9") (pin "4") (pinfunction "4_4") (pintype "passive"))
    )
    (net (code "112") (name "/PI_36") (class "Default")
      (node (ref "H_PIO") (pin "4") (pinfunction "4_4") (pintype "passive"))
      (node (ref "P10") (pin "1") (pinfunction "1_1") (pintype "passive"))
    )
    (net (code "113") (name "/PI_38") (class "Default")
      (node (ref "H_PIO") (pin "2") (pinfunction "2_2") (pintype "passive"))
      (node (ref "P10") (pin "2") (pinfunction "2_2") (pintype "passive"))
    )
    (net (code "114") (name "/PI_40") (class "Default")
      (node (ref "H_PIO") (pin "1") (pinfunction "1_1") (pintype "passive"))
      (node (ref "P10") (pin "3") (pinfunction "3_3") (pintype "passive"))
    )
    (net (code "115") (name "/PI_HS_1") (class "Default")
      (node (ref "H_PSW") (pin "1") (pinfunction "1_1") (pintype "passive"))
      (node (ref "P6") (pin "3") (pinfunction "3_3") (pintype "passive"))
    )
    (net (code "116") (name "/PI_HS_2") (class "Default")
      (node (ref "H_PSW") (pin "3") (pinfunction "3_3") (pintype "passive"))
      (node (ref "P4") (pin "1") (pinfunction "1_1") (pintype "passive"))
    )
    (net (code "117") (name "/PI_HS_3") (class "Default")
      (node (ref "H_PSW") (pin "5") (pinfunction "5_5") (pintype "passive"))
      (node (ref "P3") (pin "3") (pinfunction "3_3") (pintype "passive"))
    )
    (net (code "118") (name "/PI_HS_4") (class "Default")
      (node (ref "H_PSW") (pin "7") (pinfunction "7_7") (pintype "passive"))
      (node (ref "P6") (pin "1") (pinfunction "1_1") (pintype "passive"))
    )
    (net (code "119") (name "/PI_HS_5") (class "Default")
      (node (ref "H_PSW") (pin "9") (pinfunction "9_9") (pintype "passive"))
      (node (ref "P5") (pin "3") (pinfunction "3_3") (pintype "passive"))
    )
    (net (code "120") (name "/PI_HS_6") (class "Default")
      (node (ref "H_PSW") (pin "11") (pinfunction "11_11") (pintype "passive"))
      (node (ref "P4") (pin "3") (pinfunction "3_3") (pintype "passive"))
    )
    (net (code "121") (name "/PI_HS_7") (class "Default")
      (node (ref "H_PSW") (pin "13") (pinfunction "13_13") (pintype "passive"))
      (node (ref "P5") (pin "1") (pinfunction "1_1") (pintype "passive"))
    )
    (net (code "122") (name "/PI_HS_8") (class "Default")
      (node (ref "H_PSW") (pin "15") (pinfunction "15_15") (pintype "passive"))
      (node (ref "P3") (pin "1") (pinfunction "1_1") (pintype "passive"))
    )
    (net (code "124") (name "/PI_LS_1") (class "Default")
      (node (ref "H_PSW") (pin "2") (pinfunction "2_2") (pintype "passive"))
      (node (ref "P6") (pin "4") (pinfunction "4_4") (pintype "passive"))
    )
    (net (code "125") (name "/PI_LS_2") (class "Default")
      (node (ref "H_PSW") (pin "4") (pinfunction "4_4") (pintype "passive"))
      (node (ref "P4") (pin "2") (pinfunction "2_2") (pintype "passive"))
    )
    (net (code "126") (name "/PI_LS_3") (class "Default")
      (node (ref "H_PSW") (pin "6") (pinfunction "6_6") (pintype "passive"))
      (node (ref "P3") (pin "4") (pinfunction "4_4") (pintype "passive"))
    )
    (net (code "127") (name "/PI_LS_4") (class "Default")
      (node (ref "H_PSW") (pin "8") (pinfunction "8_8") (pintype "passive"))
      (node (ref "P6") (pin "2") (pinfunction "2_2") (pintype "passive"))
    )
    (net (code "128") (name "/PI_LS_5") (class "Default")
      (node (ref "H_PSW") (pin "10") (pinfunction "10_10") (pintype "passive"))
      (node (ref "P5") (pin "4") (pinfunction "4_4") (pintype "passive"))
    )
    (net (code "129") (name "/PI_LS_6") (class "Default")
      (node (ref "H_PSW") (pin "12") (pinfunction "12_12") (pintype "passive"))
      (node (ref "P4") (pin "4") (pinfunction "4_4") (pintype "passive"))
    )
    (net (code "130") (name "/PI_LS_7") (class "Default")
      (node (ref "H_PSW") (pin "14") (pinfunction "14_14") (pintype "passive"))
      (node (ref "P5") (pin "2") (pinfunction "2_2") (pintype "passive"))
    )
    (net (code "131") (name "/PI_LS_8") (class "Default")
      (node (ref "H_PSW") (pin "16") (pinfunction "16_16") (pintype "passive"))
      (node (ref "P3") (pin "2") (pinfunction "2_2") (pintype "passive"))
    )
    (net (code "133") (name "/PI_RX") (class "Default")
      (node (ref "H_PIO") (pin "16") (pinfunction "16_16") (pintype "passive"))
      (node (ref "P10") (pin "6") (pinfunction "6_6") (pintype "passive"))
    )
    (net (code "134") (name "/PI_TX") (class "Default")
      (node (ref "H_PIO") (pin "18") (pinfunction "18_18") (pintype "passive"))
      (node (ref "P10") (pin "5") (pinfunction "5_5") (pintype "passive"))
    )
    (net (code "135") (name "/PWM1") (class "Default")
      (node (ref "H_ACOMS") (pin "12") (pinfunction "12_12") (pintype "passive"))
      (node (ref "P21") (pin "1") (pinfunction "1_1") (pintype "passive"))
    )
    (net (code "136") (name "/PWM2") (class "Default")
      (node (ref "H_ACOMS") (pin "10") (pinfunction "10_10") (pintype "passive"))
      (node (ref "P21") (pin "2") (pinfunction "2_2") (pintype "passive"))
    )
    (net (code "137") (name "/SCK") (class "Default")
      (node (ref "H_ACOMS") (pin "15") (pinfunction "15_15") (pintype "passive"))
      (node (ref "P22") (pin "3") (pinfunction "3_3") (pintype "passive"))
    )
    (net (code "138") (name "/SS") (class "Default")
      (node (ref "H_ACOMS") (pin "16") (pinfunction "16_16") (pintype "passive"))
      (node (ref "P22") (pin "4") (pinfunction "4_4") (pintype "passive"))
    )
    (net (code "139") (name "/SSDI-12") (class "Default")
      (node (ref "H_ACOMS") (pin "9") (pinfunction "9_9") (pintype "passive"))
      (node (ref "P21") (pin "3") (pinfunction "3_3") (pintype "passive"))
    )
    (net (code "140") (name "/ard_scl_21") (class "Default")
      (node (ref "H_ACOMS") (pin "8") (pinfunction "8_8") (pintype "passive"))
      (node (ref "P20") (pin "3") (pinfunction "3_3") (pintype "passive"))
    )
    (net (code "141") (name "/ard_sda_20") (class "Default")
      (node (ref "H_ACOMS") (pin "7") (pinfunction "7_7") (pintype "passive"))
      (node (ref "P20") (pin "4") (pinfunction "4_4") (pintype "passive"))
    )
    (net (code "142") (name "/tca_sc0") (class "Default")
      (node (ref "H_TCA") (pin "3") (pinfunction "3_3") (pintype "passive"))
      (node (ref "P11") (pin "2") (pinfunction "2_2") (pintype "passive"))
    )
    (net (code "143") (name "/tca_sc1") (class "Default")
      (node (ref "H_TCA") (pin "1") (pinfunction "1_1") (pintype "passive"))
      (node (ref "P11") (pin "4") (pinfunction "4_4") (pintype "passive"))
    )
    (net (code "144") (name "/tca_sc2") (class "Default")
      (node (ref "H_TCA") (pin "5") (pinfunction "5_5") (pintype "passive"))
      (node (ref "P12") (pin "2") (pinfunction "2_2") (pintype "passive"))
    )
    (net (code "145") (name "/tca_sc3") (class "Default")
      (node (ref "H_TCA") (pin "7") (pinfunction "7_7") (pintype "passive"))
      (node (ref "P12") (pin "4") (pinfunction "4_4") (pintype "passive"))
    )
    (net (code "146") (name "/tca_sc4") (class "Default")
      (node (ref "H_TCA") (pin "9") (pinfunction "9_9") (pintype "passive"))
      (node (ref "P13") (pin "2") (pinfunction "2_2") (pintype "passive"))
    )
    (net (code "147") (name "/tca_sc5") (class "Default")
      (node (ref "H_TCA") (pin "11") (pinfunction "11_11") (pintype "passive"))
      (node (ref "P13") (pin "4") (pinfunction "4_4") (pintype "passive"))
    )
    (net (code "148") (name "/tca_sc6") (class "Default")
      (node (ref "H_TCA") (pin "13") (pinfunction "13_13") (pintype "passive"))
      (node (ref "P14") (pin "2") (pinfunction "2_2") (pintype "passive"))
    )
    (net (code "149") (name "/tca_sc7") (class "Default")
      (node (ref "H_TCA") (pin "15") (pinfunction "15_15") (pintype "passive"))
      (node (ref "P14") (pin "4") (pinfunction "4_4") (pintype "passive"))
    )
    (net (code "150") (name "/tca_sd0") (class "Default")
      (node (ref "H_TCA") (pin "4") (pinfunction "4_4") (pintype "passive"))
      (node (ref "P11") (pin "1") (pinfunction "1_1") (pintype "passive"))
    )
    (net (code "151") (name "/tca_sd1") (class "Default")
      (node (ref "H_TCA") (pin "2") (pinfunction "2_2") (pintype "passive"))
      (node (ref "P11") (pin "3") (pinfunction "3_3") (pintype "passive"))
    )
    (net (code "152") (name "/tca_sd2") (class "Default")
      (node (ref "H_TCA") (pin "6") (pinfunction "6_6") (pintype "passive"))
      (node (ref "P12") (pin "1") (pinfunction "1_1") (pintype "passive"))
    )
    (net (code "153") (name "/tca_sd3") (class "Default")
      (node (ref "H_TCA") (pin "8") (pinfunction "8_8") (pintype "passive"))
      (node (ref "P12") (pin "3") (pinfunction "3_3") (pintype "passive"))
    )
    (net (code "154") (name "/tca_sd4") (class "Default")
      (node (ref "H_TCA") (pin "10") (pinfunction "10_10") (pintype "passive"))
      (node (ref "P13") (pin "1") (pinfunction "1_1") (pintype "passive"))
    )
    (net (code "155") (name "/tca_sd5") (class "Default")
      (node (ref "H_TCA") (pin "12") (pinfunction "12_12") (pintype "passive"))
      (node (ref "P13") (pin "3") (pinfunction "3_3") (pintype "passive"))
    )
    (net (code "156") (name "/tca_sd6") (class "Default")
      (node (ref "H_TCA") (pin "14") (pinfunction "14_14") (pintype "passive"))
      (node (ref "P14") (pin "1") (pinfunction "1_1") (pintype "passive"))
    )
    (net (code "157") (name "/tca_sd7") (class "Default")
      (node (ref "H_TCA") (pin "16") (pinfunction "16_16") (pintype "passive"))
      (node (ref "P14") (pin "3") (pinfunction "3_3") (pintype "passive"))
    )
    (net (code "158") (name "3.3V") (class "Default")
      (node (ref "H_ASW2P") (pin "4") (pinfunction "4_4") (pintype "passive"))
      (node (ref "P1") (pin "3") (pinfunction "3_3") (pintype "passive"))
    )
    (net (code "159") (name "5V") (class "Default")
      (node (ref "H_ASW2P") (pin "2") (pinfunction "2_2") (pintype "passive"))
      (node (ref "P1") (pin "1") (pinfunction "1_1") (pintype "passive"))
    )
    (net (code "160") (name "12V") (class "Default")
      (node (ref "H_ASW2P") (pin "1") (pinfunction "1_1") (pintype "passive"))
      (node (ref "P2") (pin "3") (pinfunction "3_3") (pintype "passive"))
    )
    (net (code "161") (name "GND") (class "Default")
      (node (ref "H_ACOMS") (pin "11") (pinfunction "11_11") (pintype "passive"))
      (node (ref "H_ASW2P") (pin "3") (pinfunction "3_3") (pintype "passive"))
      (node (ref "H_PIO") (pin "17") (pinfunction "17_17") (pintype "passive"))
      (node (ref "P10") (pin "4") (pinfunction "4_4") (pintype "passive"))
      (node (ref "P2") (pin "1") (pinfunction "1_1") (pintype "passive"))
      (node (ref "P21") (pin "4") (pinfunction "4_4") (pintype "passive"))
    )
    (net (code "162") (name "unconnected-(MH1-Pad0)") (class "Default")
      (node (ref "MH1") (pin "0") (pinfunction "0_0") (pintype "passive+no_connect"))
    )
    (net (code "163") (name "unconnected-(MH2-Pad0)") (class "Default")
      (node (ref "MH2") (pin "0") (pinfunction "0_0") (pintype "passive+no_connect"))
    )
    (net (code "164") (name "unconnected-(MH3-Pad0)") (class "Default")
      (node (ref "MH3") (pin "0") (pinfunction "0_0") (pintype "passive+no_connect"))
    )
    (net (code "165") (name "unconnected-(MH4-Pad0)") (class "Default")
      (node (ref "MH4") (pin "0") (pinfunction "0_0") (pintype "passive+no_connect"))
    )
    (net (code "166") (name "unconnected-(MH5-Pad0)") (class "Default")
      (node (ref "MH5") (pin "0") (pinfunction "0_0") (pintype "passive+no_connect"))
    )
    (net (code "167") (name "unconnected-(MH6-Pad0)") (class "Default")
      (node (ref "MH6") (pin "0") (pinfunction "0_0") (pintype "passive+no_connect"))
    )
    (net (code "168") (name "unconnected-(MH7-Pad0)") (class "Default")
      (node (ref "MH7") (pin "0") (pinfunction "0_0") (pintype "passive+no_connect"))
    )
    (net (code "169") (name "unconnected-(TD1-Pad0)") (class "Default")
      (node (ref "TD1") (pin "0") (pinfunction "0_0") (pintype "passive"))
    )
    (net (code "170") (name "unconnected-(TD2-Pad0)") (class "Default")
      (node (ref "TD2") (pin "0") (pinfunction "0_0") (pintype "passive"))
    )
    (net (code "171") (name "unconnected-(TD3-Pad0)") (class "Default")
      (node (ref "TD3") (pin "0") (pinfunction "0_0") (pintype "passive"))
    )
    (net (code "172") (name "unconnected-(TD4-Pad0)") (class "Default")
      (node (ref "TD4") (pin "0") (pinfunction "0_0") (pintype "passive"))
    )
    (net (code "173") (name "unconnected-(TD5-Pad0)") (class "Default")
      (node (ref "TD5") (pin "0") (pinfunction "0_0") (pintype "passive"))
    )
    (net (code "174") (name "unconnected-(TD6-Pad0)") (class "Default")
      (node (ref "TD6") (pin "0") (pinfunction "0_0") (pintype "passive"))
    )
    (net (code "175") (name "unconnected-(TD7-Pad0)") (class "Default")
      (node (ref "TD7") (pin "0") (pinfunction "0_0") (pintype "passive"))
    )
    (net (code "176") (name "unconnected-(TD8-Pad0)") (class "Default")
      (node (ref "TD8") (pin "0") (pinfunction "0_0") (pintype "passive"))
    )
    (net (code "177") (name "unconnected-(TD9-Pad0)") (class "Default")
      (node (ref "TD9") (pin "0") (pinfunction "0_0") (pintype "passive"))
    )
    (net (code "178") (name "unconnected-(TD10-Pad0)") (class "Default")
      (node (ref "TD10") (pin "0") (pinfunction "0_0") (pintype "passive"))
    )
    (net (code "179") (name "unconnected-(TD11-Pad0)") (class "Default")
      (node (ref "TD11") (pin "0") (pinfunction "0_0") (pintype "passive"))
    )
  )
)
